# motoko_ice_dragon.net
KiCad netlist of a schematic drawn in EAGLE
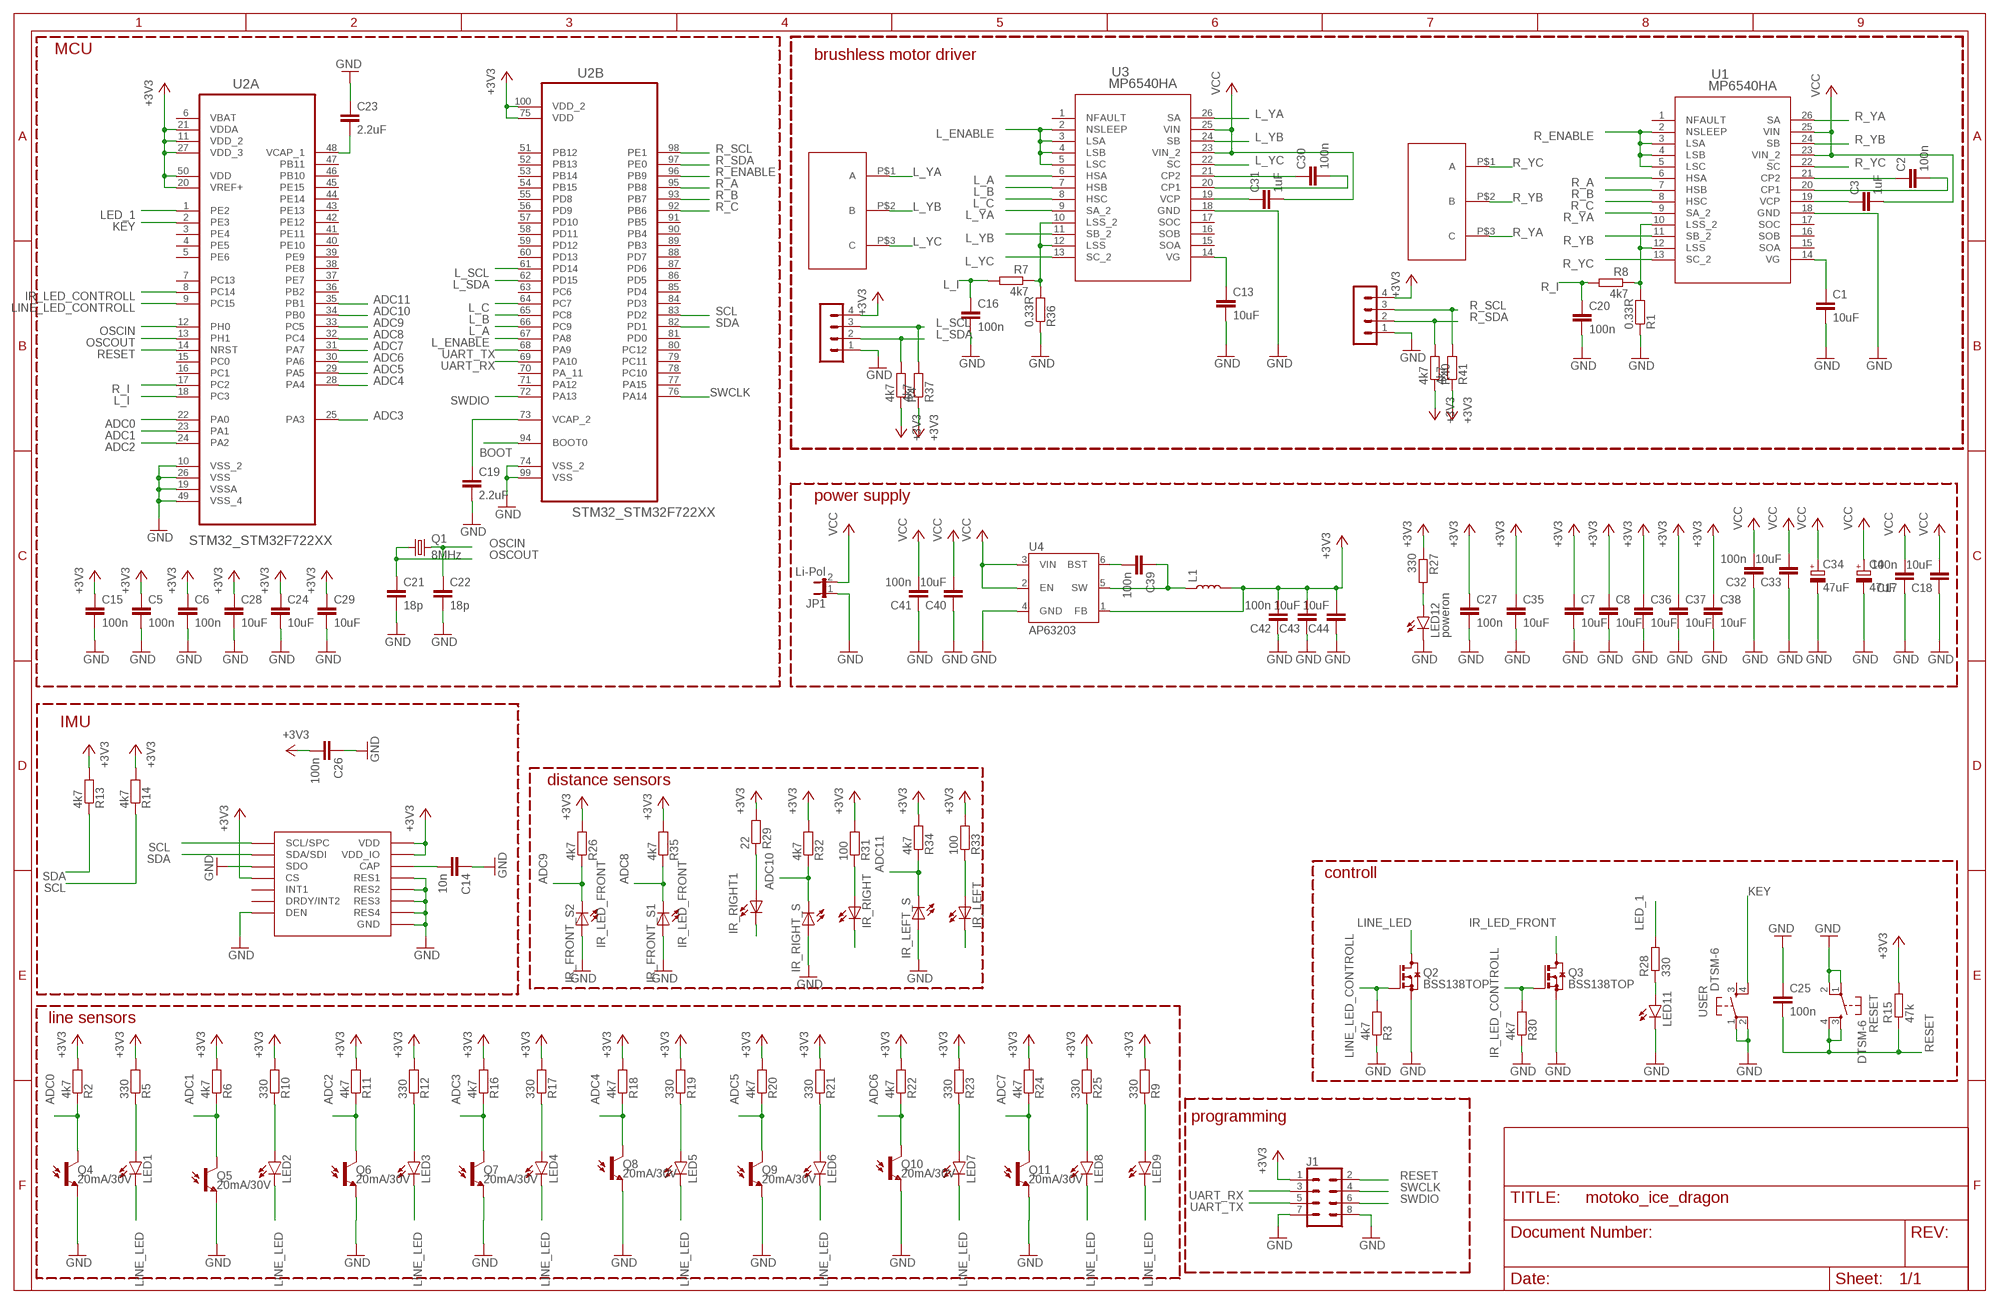
[diagram p0: schematic, sheet 1]

(export (version "E")
  (design (tool "Eeschema 10.0.6"))
  (components
    (comp (ref "C1")
      (value "10uF")
      (footprint "eagle-import:C0805")
      (libsource (lib "eagle-import") (part "C-EUC0805"))
    )
    (comp (ref "C2")
      (value "100n")
      (footprint "eagle-import:C0805")
      (libsource (lib "eagle-import") (part "C-EUC0805"))
    )
    (comp (ref "C3")
      (value "1uF")
      (footprint "eagle-import:C0805")
      (libsource (lib "eagle-import") (part "C-EUC0805"))
    )
    (comp (ref "C4")
      (value "47uF")
      (footprint "eagle-import:140CLH-1010")
      (libsource (lib "eagle-import") (part "CPOL-EU140CLH-1010"))
    )
    (comp (ref "C5")
      (value "100n")
      (footprint "eagle-import:C0805")
      (libsource (lib "eagle-import") (part "C-EUC0805"))
    )
    (comp (ref "C6")
      (value "100n")
      (footprint "eagle-import:C0805")
      (libsource (lib "eagle-import") (part "C-EUC0805"))
    )
    (comp (ref "C7")
      (value "10uF")
      (footprint "eagle-import:C0805")
      (libsource (lib "eagle-import") (part "C-EUC0805"))
    )
    (comp (ref "C8")
      (value "10uF")
      (footprint "eagle-import:C0805")
      (libsource (lib "eagle-import") (part "C-EUC0805"))
    )
    (comp (ref "C13")
      (value "10uF")
      (footprint "eagle-import:C0805")
      (libsource (lib "eagle-import") (part "C-EUC0805"))
    )
    (comp (ref "C14")
      (value "10n")
      (footprint "eagle-import:C0805")
      (libsource (lib "eagle-import") (part "C-EUC0805"))
    )
    (comp (ref "C15")
      (value "100n")
      (footprint "eagle-import:C0805")
      (libsource (lib "eagle-import") (part "C-EUC0805"))
    )
    (comp (ref "C16")
      (value "100n")
      (footprint "eagle-import:C0805")
      (libsource (lib "eagle-import") (part "C-EUC0805"))
    )
    (comp (ref "C17")
      (value "100n")
      (footprint "eagle-import:C0805")
      (libsource (lib "eagle-import") (part "C-EUC0805"))
    )
    (comp (ref "C18")
      (value "10uF")
      (footprint "eagle-import:C0805")
      (libsource (lib "eagle-import") (part "C-EUC0805"))
    )
    (comp (ref "C19")
      (value "2.2uF")
      (footprint "eagle-import:C0805")
      (libsource (lib "eagle-import") (part "C-EUC0805"))
    )
    (comp (ref "C20")
      (value "100n")
      (footprint "eagle-import:C0805")
      (libsource (lib "eagle-import") (part "C-EUC0805"))
    )
    (comp (ref "C21")
      (value "18p")
      (footprint "eagle-import:C0805")
      (libsource (lib "eagle-import") (part "C-EUC0805"))
    )
    (comp (ref "C22")
      (value "18p")
      (footprint "eagle-import:C0805")
      (libsource (lib "eagle-import") (part "C-EUC0805"))
    )
    (comp (ref "C23")
      (value "2.2uF")
      (footprint "eagle-import:C0805")
      (libsource (lib "eagle-import") (part "C-EUC0805"))
    )
    (comp (ref "C24")
      (value "10uF")
      (footprint "eagle-import:C0805")
      (libsource (lib "eagle-import") (part "C-EUC0805"))
    )
    (comp (ref "C25")
      (value "100n")
      (footprint "eagle-import:C0805")
      (libsource (lib "eagle-import") (part "C-EUC0805"))
    )
    (comp (ref "C26")
      (value "100n")
      (footprint "eagle-import:C0805")
      (libsource (lib "eagle-import") (part "C-EUC0805"))
    )
    (comp (ref "C27")
      (value "100n")
      (footprint "eagle-import:C0805")
      (libsource (lib "eagle-import") (part "C-EUC0805"))
    )
    (comp (ref "C28")
      (value "10uF")
      (footprint "eagle-import:C0805")
      (libsource (lib "eagle-import") (part "C-EUC0805"))
    )
    (comp (ref "C29")
      (value "10uF")
      (footprint "eagle-import:C0805")
      (libsource (lib "eagle-import") (part "C-EUC0805"))
    )
    (comp (ref "C30")
      (value "100n")
      (footprint "eagle-import:C0805")
      (libsource (lib "eagle-import") (part "C-EUC0805"))
    )
    (comp (ref "C31")
      (value "1uF")
      (footprint "eagle-import:C0805")
      (libsource (lib "eagle-import") (part "C-EUC0805"))
    )
    (comp (ref "C32")
      (value "100n")
      (footprint "eagle-import:C0805")
      (libsource (lib "eagle-import") (part "C-EUC0805"))
    )
    (comp (ref "C33")
      (value "10uF")
      (footprint "eagle-import:C0805")
      (libsource (lib "eagle-import") (part "C-EUC0805"))
    )
    (comp (ref "C34")
      (value "47uF")
      (footprint "eagle-import:140CLH-1010")
      (libsource (lib "eagle-import") (part "CPOL-EU140CLH-1010"))
    )
    (comp (ref "C35")
      (value "10uF")
      (footprint "eagle-import:C0805")
      (libsource (lib "eagle-import") (part "C-EUC0805"))
    )
    (comp (ref "C36")
      (value "10uF")
      (footprint "eagle-import:C0805")
      (libsource (lib "eagle-import") (part "C-EUC0805"))
    )
    (comp (ref "C37")
      (value "10uF")
      (footprint "eagle-import:C0805")
      (libsource (lib "eagle-import") (part "C-EUC0805"))
    )
    (comp (ref "C38")
      (value "10uF")
      (footprint "eagle-import:C0805")
      (libsource (lib "eagle-import") (part "C-EUC0805"))
    )
    (comp (ref "C39")
      (value "100n")
      (footprint "eagle-import:C0805")
      (libsource (lib "eagle-import") (part "C-EUC0805"))
    )
    (comp (ref "C40")
      (value "10uF")
      (footprint "eagle-import:C0805")
      (libsource (lib "eagle-import") (part "C-EUC0805"))
    )
    (comp (ref "C41")
      (value "100n")
      (footprint "eagle-import:C0805")
      (libsource (lib "eagle-import") (part "C-EUC0805"))
    )
    (comp (ref "C42")
      (value "100n")
      (footprint "eagle-import:C0805")
      (libsource (lib "eagle-import") (part "C-EUC0805"))
    )
    (comp (ref "C43")
      (value "10uF")
      (footprint "eagle-import:C0805")
      (libsource (lib "eagle-import") (part "C-EUC0805"))
    )
    (comp (ref "C44")
      (value "10uF")
      (footprint "eagle-import:C0805")
      (libsource (lib "eagle-import") (part "C-EUC0805"))
    )
    (comp (ref "IR_FRONT_S1")
      (value "LED5MM")
      (footprint "eagle-import:LED5MM")
      (libsource (lib "eagle-import") (part "my_parts_LED5MM"))
    )
    (comp (ref "IR_FRONT_S2")
      (value "LED5MM")
      (footprint "eagle-import:LED5MM")
      (libsource (lib "eagle-import") (part "my_parts_LED5MM"))
    )
    (comp (ref "IR_LEFT")
      (value "LED5MM")
      (footprint "eagle-import:LED5MM")
      (libsource (lib "eagle-import") (part "my_parts_LED5MM"))
    )
    (comp (ref "IR_LEFT_S")
      (value "LED5MM")
      (footprint "eagle-import:LED5MM")
      (libsource (lib "eagle-import") (part "my_parts_LED5MM"))
    )
    (comp (ref "IR_RIGHT")
      (value "LED5MM")
      (footprint "eagle-import:LED5MM")
      (libsource (lib "eagle-import") (part "my_parts_LED5MM"))
    )
    (comp (ref "IR_RIGHT1")
      (value "LED5MM")
      (footprint "eagle-import:LED5MM")
      (libsource (lib "eagle-import") (part "my_parts_LED5MM"))
    )
    (comp (ref "IR_RIGHT_S")
      (value "LED5MM")
      (footprint "eagle-import:LED5MM")
      (libsource (lib "eagle-import") (part "my_parts_LED5MM"))
    )
    (comp (ref "J1")
      (value "CONN_04X2")
      (footprint "eagle-import:2X4")
      (libsource (lib "eagle-import") (part "CONN_04X2"))
    )
    (comp (ref "JP1")
      (value "Li-Pol")
      (footprint "eagle-import:JP1")
      (libsource (lib "eagle-import") (part "JP1E"))
    )
    (comp (ref "L1")
      (value "4.7uH, TYS50204R7N-10")
      (footprint "eagle-import:CR54")
      (libsource (lib "eagle-import") (part "INDUCTOR-CR54-3.3UH"))
    )
    (comp (ref "LED1")
      (value "LEDCHIPLED_1206")
      (footprint "eagle-import:CHIPLED_1206")
      (libsource (lib "eagle-import") (part "LEDCHIPLED_1206"))
    )
    (comp (ref "LED2")
      (value "LEDCHIPLED_1206")
      (footprint "eagle-import:CHIPLED_1206")
      (libsource (lib "eagle-import") (part "LEDCHIPLED_1206"))
    )
    (comp (ref "LED3")
      (value "LEDCHIPLED_1206")
      (footprint "eagle-import:CHIPLED_1206")
      (libsource (lib "eagle-import") (part "LEDCHIPLED_1206"))
    )
    (comp (ref "LED4")
      (value "LEDCHIPLED_1206")
      (footprint "eagle-import:CHIPLED_1206")
      (libsource (lib "eagle-import") (part "LEDCHIPLED_1206"))
    )
    (comp (ref "LED5")
      (value "LEDCHIPLED_1206")
      (footprint "eagle-import:CHIPLED_1206")
      (libsource (lib "eagle-import") (part "LEDCHIPLED_1206"))
    )
    (comp (ref "LED6")
      (value "LEDCHIPLED_1206")
      (footprint "eagle-import:CHIPLED_1206")
      (libsource (lib "eagle-import") (part "LEDCHIPLED_1206"))
    )
    (comp (ref "LED7")
      (value "LEDCHIPLED_1206")
      (footprint "eagle-import:CHIPLED_1206")
      (libsource (lib "eagle-import") (part "LEDCHIPLED_1206"))
    )
    (comp (ref "LED8")
      (value "LEDCHIPLED_1206")
      (footprint "eagle-import:CHIPLED_1206")
      (libsource (lib "eagle-import") (part "LEDCHIPLED_1206"))
    )
    (comp (ref "LED9")
      (value "LEDCHIPLED_1206")
      (footprint "eagle-import:CHIPLED_1206")
      (libsource (lib "eagle-import") (part "LEDCHIPLED_1206"))
    )
    (comp (ref "LED11")
      (value "LEDCHIPLED_1206")
      (footprint "eagle-import:CHIPLED_1206")
      (libsource (lib "eagle-import") (part "LEDCHIPLED_1206"))
    )
    (comp (ref "LED12")
      (value "poweron")
      (footprint "eagle-import:CHIPLED_1206")
      (libsource (lib "eagle-import") (part "LEDCHIPLED_1206"))
    )
    (comp (ref "LSM6DS1")
      (value "ST_L3GD20H")
      (footprint "eagle-import:ST_LGA16L")
      (libsource (lib "eagle-import") (part "ST_L3GD20H"))
    )
    (comp (ref "L_ENCODER")
      (value "MA04-1")
      (footprint "eagle-import:MA04-1")
      (libsource (lib "eagle-import") (part "MA04-1"))
    )
    (comp (ref "L_ENCODER1")
      (value "MA04-1")
      (footprint "eagle-import:MA04-1")
      (libsource (lib "eagle-import") (part "MA04-1"))
    )
    (comp (ref "Q1")
      (value "8MHz")
      (footprint "eagle-import:CTS406")
      (libsource (lib "eagle-import") (part "CRYSTALCTS406"))
    )
    (comp (ref "Q2")
      (value "BSS138TOP")
      (footprint "eagle-import:SOT23")
      (libsource (lib "eagle-import") (part "BSS138TOP"))
    )
    (comp (ref "Q3")
      (value "BSS138TOP")
      (footprint "eagle-import:SOT23")
      (libsource (lib "eagle-import") (part "BSS138TOP"))
    )
    (comp (ref "Q4")
      (value "20mA/30V")
      (footprint "eagle-import:PT17-21C-L41-TR8")
      (libsource (lib "eagle-import") (part "PHOTOTRANSISTORPT17-21C-L41-TR8"))
    )
    (comp (ref "Q5")
      (value "20mA/30V")
      (footprint "eagle-import:PT17-21C-L41-TR8")
      (libsource (lib "eagle-import") (part "PHOTOTRANSISTORPT17-21C-L41-TR8"))
    )
    (comp (ref "Q6")
      (value "20mA/30V")
      (footprint "eagle-import:PT17-21C-L41-TR8")
      (libsource (lib "eagle-import") (part "PHOTOTRANSISTORPT17-21C-L41-TR8"))
    )
    (comp (ref "Q7")
      (value "20mA/30V")
      (footprint "eagle-import:PT17-21C-L41-TR8")
      (libsource (lib "eagle-import") (part "PHOTOTRANSISTORPT17-21C-L41-TR8"))
    )
    (comp (ref "Q8")
      (value "20mA/30V")
      (footprint "eagle-import:PT17-21C-L41-TR8")
      (libsource (lib "eagle-import") (part "PHOTOTRANSISTORPT17-21C-L41-TR8"))
    )
    (comp (ref "Q9")
      (value "20mA/30V")
      (footprint "eagle-import:PT17-21C-L41-TR8")
      (libsource (lib "eagle-import") (part "PHOTOTRANSISTORPT17-21C-L41-TR8"))
    )
    (comp (ref "Q10")
      (value "20mA/30V")
      (footprint "eagle-import:PT17-21C-L41-TR8")
      (libsource (lib "eagle-import") (part "PHOTOTRANSISTORPT17-21C-L41-TR8"))
    )
    (comp (ref "Q11")
      (value "20mA/30V")
      (footprint "eagle-import:PT17-21C-L41-TR8")
      (libsource (lib "eagle-import") (part "PHOTOTRANSISTORPT17-21C-L41-TR8"))
    )
    (comp (ref "R1")
      (value "0.33R")
      (footprint "eagle-import:M0805")
      (libsource (lib "eagle-import") (part "R-EU_M0805"))
    )
    (comp (ref "R2")
      (value "4k7")
      (footprint "eagle-import:M0805")
      (libsource (lib "eagle-import") (part "R-EU_M0805"))
    )
    (comp (ref "R3")
      (value "4k7")
      (footprint "eagle-import:M0805")
      (libsource (lib "eagle-import") (part "R-EU_M0805"))
    )
    (comp (ref "R4")
      (value "4k7")
      (footprint "eagle-import:M0805")
      (libsource (lib "eagle-import") (part "R-EU_M0805"))
    )
    (comp (ref "R5")
      (value "330")
      (footprint "eagle-import:M0805")
      (libsource (lib "eagle-import") (part "R-EU_M0805"))
    )
    (comp (ref "R6")
      (value "4k7")
      (footprint "eagle-import:M0805")
      (libsource (lib "eagle-import") (part "R-EU_M0805"))
    )
    (comp (ref "R7")
      (value "4k7")
      (footprint "eagle-import:M0805")
      (libsource (lib "eagle-import") (part "R-EU_M0805"))
    )
    (comp (ref "R8")
      (value "4k7")
      (footprint "eagle-import:M0805")
      (libsource (lib "eagle-import") (part "R-EU_M0805"))
    )
    (comp (ref "R9")
      (value "330")
      (footprint "eagle-import:M0805")
      (libsource (lib "eagle-import") (part "R-EU_M0805"))
    )
    (comp (ref "R10")
      (value "330")
      (footprint "eagle-import:M0805")
      (libsource (lib "eagle-import") (part "R-EU_M0805"))
    )
    (comp (ref "R11")
      (value "4k7")
      (footprint "eagle-import:M0805")
      (libsource (lib "eagle-import") (part "R-EU_M0805"))
    )
    (comp (ref "R12")
      (value "330")
      (footprint "eagle-import:M0805")
      (libsource (lib "eagle-import") (part "R-EU_M0805"))
    )
    (comp (ref "R13")
      (value "4k7")
      (footprint "eagle-import:M0805")
      (libsource (lib "eagle-import") (part "R-EU_M0805"))
    )
    (comp (ref "R14")
      (value "4k7")
      (footprint "eagle-import:M0805")
      (libsource (lib "eagle-import") (part "R-EU_M0805"))
    )
    (comp (ref "R15")
      (value "47k")
      (footprint "eagle-import:M0805")
      (libsource (lib "eagle-import") (part "R-EU_M0805"))
    )
    (comp (ref "R16")
      (value "4k7")
      (footprint "eagle-import:M0805")
      (libsource (lib "eagle-import") (part "R-EU_M0805"))
    )
    (comp (ref "R17")
      (value "330")
      (footprint "eagle-import:M0805")
      (libsource (lib "eagle-import") (part "R-EU_M0805"))
    )
    (comp (ref "R18")
      (value "4k7")
      (footprint "eagle-import:M0805")
      (libsource (lib "eagle-import") (part "R-EU_M0805"))
    )
    (comp (ref "R19")
      (value "330")
      (footprint "eagle-import:M0805")
      (libsource (lib "eagle-import") (part "R-EU_M0805"))
    )
    (comp (ref "R20")
      (value "4k7")
      (footprint "eagle-import:M0805")
      (libsource (lib "eagle-import") (part "R-EU_M0805"))
    )
    (comp (ref "R21")
      (value "330")
      (footprint "eagle-import:M0805")
      (libsource (lib "eagle-import") (part "R-EU_M0805"))
    )
    (comp (ref "R22")
      (value "4k7")
      (footprint "eagle-import:M0805")
      (libsource (lib "eagle-import") (part "R-EU_M0805"))
    )
    (comp (ref "R23")
      (value "330")
      (footprint "eagle-import:M0805")
      (libsource (lib "eagle-import") (part "R-EU_M0805"))
    )
    (comp (ref "R24")
      (value "4k7")
      (footprint "eagle-import:M0805")
      (libsource (lib "eagle-import") (part "R-EU_M0805"))
    )
    (comp (ref "R25")
      (value "330")
      (footprint "eagle-import:M0805")
      (libsource (lib "eagle-import") (part "R-EU_M0805"))
    )
    (comp (ref "R26")
      (value "4k7")
      (footprint "eagle-import:M0805")
      (libsource (lib "eagle-import") (part "R-EU_M0805"))
    )
    (comp (ref "R27")
      (value "330")
      (footprint "eagle-import:M0805")
      (libsource (lib "eagle-import") (part "R-EU_M0805"))
    )
    (comp (ref "R28")
      (value "330")
      (footprint "eagle-import:M0805")
      (libsource (lib "eagle-import") (part "R-EU_M0805"))
    )
    (comp (ref "R29")
      (value "22")
      (footprint "eagle-import:M0805")
      (libsource (lib "eagle-import") (part "R-EU_M0805"))
    )
    (comp (ref "R30")
      (value "4k7")
      (footprint "eagle-import:M0805")
      (libsource (lib "eagle-import") (part "R-EU_M0805"))
    )
    (comp (ref "R31")
      (value "100")
      (footprint "eagle-import:M0805")
      (libsource (lib "eagle-import") (part "R-EU_M0805"))
    )
    (comp (ref "R32")
      (value "4k7")
      (footprint "eagle-import:M0805")
      (libsource (lib "eagle-import") (part "R-EU_M0805"))
    )
    (comp (ref "R33")
      (value "100")
      (footprint "eagle-import:M0805")
      (libsource (lib "eagle-import") (part "R-EU_M0805"))
    )
    (comp (ref "R34")
      (value "4k7")
      (footprint "eagle-import:M0805")
      (libsource (lib "eagle-import") (part "R-EU_M0805"))
    )
    (comp (ref "R35")
      (value "4k7")
      (footprint "eagle-import:M0805")
      (libsource (lib "eagle-import") (part "R-EU_M0805"))
    )
    (comp (ref "R36")
      (value "0.33R")
      (footprint "eagle-import:M0805")
      (libsource (lib "eagle-import") (part "R-EU_M0805"))
    )
    (comp (ref "R37")
      (value "4k7")
      (footprint "eagle-import:M0805")
      (libsource (lib "eagle-import") (part "R-EU_M0805"))
    )
    (comp (ref "R40")
      (value "4k7")
      (footprint "eagle-import:M0805")
      (libsource (lib "eagle-import") (part "R-EU_M0805"))
    )
    (comp (ref "R41")
      (value "4k7")
      (footprint "eagle-import:M0805")
      (libsource (lib "eagle-import") (part "R-EU_M0805"))
    )
    (comp (ref "RESET")
      (value "DTSM-6")
      (footprint "eagle-import:DTSM-6")
      (libsource (lib "eagle-import") (part "DTSM-6"))
    )
    (comp (ref "U$1")
      (value "BRUSHLESS_GIMBAL_MOTOR_WHEEL")
      (footprint "eagle-import:BRUSHLESS_GIMBAL_MOTOR_WHEEL")
      (libsource (lib "eagle-import") (part "BRUSHLESS_GIMBAL_MOTOR_WHEEL"))
    )
    (comp (ref "U$2")
      (value "BRUSHLESS_GIMBAL_MOTOR_WHEEL")
      (footprint "eagle-import:BRUSHLESS_GIMBAL_MOTOR_WHEEL")
      (libsource (lib "eagle-import") (part "BRUSHLESS_GIMBAL_MOTOR_WHEEL"))
    )
    (comp (ref "U1")
      (value "MP6540HA")
      (footprint "eagle-import:QFN-5X5_MP6540HA_MNP")
      (fields (field (name "COPYRIGHT") "Copyright (C) 2018 Accelerated Designs. All rights reserved"))
      (libsource (lib "eagle-import") (part "MP6540HA"))
    )
    (comp (ref "U2")
      (value "STM32_STM32F722XX")
      (footprint "eagle-import:STM32_QFP50P1600X1600X160-100N")
      (fields (field (name "MPN") "STM32F407VET6"))
      (libsource (lib "eagle-import") (part "STM32_STM32F722XX"))
    )
    (comp (ref "U3")
      (value "MP6540HA")
      (footprint "eagle-import:QFN-5X5_MP6540HA_MNP")
      (fields (field (name "COPYRIGHT") "Copyright (C) 2018 Accelerated Designs. All rights reserved"))
      (libsource (lib "eagle-import") (part "MP6540HA"))
    )
    (comp (ref "U4")
      (value "AP63203")
      (footprint "eagle-import:SOT23-6")
      (libsource (lib "eagle-import") (part "AP63203"))
    )
    (comp (ref "USER")
      (value "DTSM-6")
      (footprint "eagle-import:DTSM-6")
      (libsource (lib "eagle-import") (part "DTSM-6"))
    )
  )
  (nets
    (net (code "1") (name "+3V3") (class "Default")
      (node (ref "C15") (pin "1") (pinfunction "1_1") (pintype "passive"))
      (node (ref "C24") (pin "1") (pinfunction "1_1") (pintype "passive"))
      (node (ref "C26") (pin "2") (pinfunction "2_2") (pintype "passive"))
      (node (ref "C27") (pin "1") (pinfunction "1_1") (pintype "passive"))
      (node (ref "C28") (pin "1") (pinfunction "1_1") (pintype "passive"))
      (node (ref "C29") (pin "1") (pinfunction "1_1") (pintype "passive"))
      (node (ref "C35") (pin "1") (pinfunction "1_1") (pintype "passive"))
      (node (ref "C36") (pin "1") (pinfunction "1_1") (pintype "passive"))
      (node (ref "C37") (pin "1") (pinfunction "1_1") (pintype "passive"))
      (node (ref "C38") (pin "1") (pinfunction "1_1") (pintype "passive"))
      (node (ref "C42") (pin "2") (pinfunction "2_2") (pintype "passive"))
      (node (ref "C43") (pin "2") (pinfunction "2_2") (pintype "passive"))
      (node (ref "C44") (pin "2") (pinfunction "2_2") (pintype "passive"))
      (node (ref "C5") (pin "1") (pinfunction "1_1") (pintype "passive"))
      (node (ref "C6") (pin "1") (pinfunction "1_1") (pintype "passive"))
      (node (ref "C7") (pin "1") (pinfunction "1_1") (pintype "passive"))
      (node (ref "C8") (pin "1") (pinfunction "1_1") (pintype "passive"))
      (node (ref "J1") (pin "1") (pinfunction "1_1") (pintype "passive"))
      (node (ref "L1") (pin "P$2") (pinfunction "2_P$2") (pintype "passive"))
      (node (ref "LSM6DS1") (pin "P$1") (pinfunction "VDD_IO_P$1") (pintype "power_in"))
      (node (ref "LSM6DS1") (pin "P$16") (pinfunction "VDD_P$16") (pintype "power_in"))
      (node (ref "LSM6DS1") (pin "P$5") (pinfunction "CS_P$5") (pintype "bidirectional"))
      (node (ref "L_ENCODER") (pin "4") (pinfunction "4_4") (pintype "passive"))
      (node (ref "L_ENCODER1") (pin "4") (pinfunction "4_4") (pintype "passive"))
      (node (ref "R10") (pin "2") (pinfunction "2_2") (pintype "passive"))
      (node (ref "R11") (pin "2") (pinfunction "2_2") (pintype "passive"))
      (node (ref "R12") (pin "2") (pinfunction "2_2") (pintype "passive"))
      (node (ref "R13") (pin "2") (pinfunction "2_2") (pintype "passive"))
      (node (ref "R14") (pin "2") (pinfunction "2_2") (pintype "passive"))
      (node (ref "R15") (pin "2") (pinfunction "2_2") (pintype "passive"))
      (node (ref "R16") (pin "2") (pinfunction "2_2") (pintype "passive"))
      (node (ref "R17") (pin "2") (pinfunction "2_2") (pintype "passive"))
      (node (ref "R18") (pin "2") (pinfunction "2_2") (pintype "passive"))
      (node (ref "R19") (pin "2") (pinfunction "2_2") (pintype "passive"))
      (node (ref "R2") (pin "2") (pinfunction "2_2") (pintype "passive"))
      (node (ref "R20") (pin "2") (pinfunction "2_2") (pintype "passive"))
      (node (ref "R21") (pin "2") (pinfunction "2_2") (pintype "passive"))
      (node (ref "R22") (pin "2") (pinfunction "2_2") (pintype "passive"))
      (node (ref "R23") (pin "2") (pinfunction "2_2") (pintype "passive"))
      (node (ref "R24") (pin "2") (pinfunction "2_2") (pintype "passive"))
      (node (ref "R25") (pin "2") (pinfunction "2_2") (pintype "passive"))
      (node (ref "R26") (pin "2") (pinfunction "2_2") (pintype "passive"))
      (node (ref "R27") (pin "1") (pinfunction "1_1") (pintype "passive"))
      (node (ref "R29") (pin "2") (pinfunction "2_2") (pintype "passive"))
      (node (ref "R31") (pin "2") (pinfunction "2_2") (pintype "passive"))
      (node (ref "R32") (pin "2") (pinfunction "2_2") (pintype "passive"))
      (node (ref "R33") (pin "2") (pinfunction "2_2") (pintype "passive"))
      (node (ref "R34") (pin "2") (pinfunction "2_2") (pintype "passive"))
      (node (ref "R35") (pin "2") (pinfunction "2_2") (pintype "passive"))
      (node (ref "R37") (pin "1") (pinfunction "1_1") (pintype "passive"))
      (node (ref "R4") (pin "1") (pinfunction "1_1") (pintype "passive"))
      (node (ref "R40") (pin "1") (pinfunction "1_1") (pintype "passive"))
      (node (ref "R41") (pin "1") (pinfunction "1_1") (pintype "passive"))
      (node (ref "R5") (pin "2") (pinfunction "2_2") (pintype "passive"))
      (node (ref "R6") (pin "2") (pinfunction "2_2") (pintype "passive"))
      (node (ref "R9") (pin "2") (pinfunction "2_2") (pintype "passive"))
      (node (ref "U2") (pin "100") (pinfunction "VDD_2_100") (pintype "power_in"))
      (node (ref "U2") (pin "11") (pinfunction "VDD_2_11") (pintype "power_in"))
      (node (ref "U2") (pin "20") (pinfunction "VREF+_20") (pintype "power_in"))
      (node (ref "U2") (pin "21") (pinfunction "VDDA_21") (pintype "power_in"))
      (node (ref "U2") (pin "27") (pinfunction "VDD_3_27") (pintype "power_in"))
      (node (ref "U2") (pin "50") (pinfunction "VDD_50") (pintype "power_in"))
      (node (ref "U2") (pin "75") (pinfunction "VDD_75") (pintype "power_in"))
      (node (ref "U4") (pin "1") (pinfunction "FB_1") (pintype "bidirectional"))
    )
    (net (code "2") (name "/ADC0") (class "Default")
      (node (ref "Q4") (pin "C") (pinfunction "C_C") (pintype "passive"))
      (node (ref "R2") (pin "1") (pinfunction "1_1") (pintype "passive"))
      (node (ref "U2") (pin "22") (pinfunction "PA0_22") (pintype "bidirectional"))
    )
    (net (code "3") (name "/ADC1") (class "Default")
      (node (ref "Q5") (pin "C") (pinfunction "C_C") (pintype "passive"))
      (node (ref "R6") (pin "1") (pinfunction "1_1") (pintype "passive"))
      (node (ref "U2") (pin "23") (pinfunction "PA1_23") (pintype "bidirectional"))
    )
    (net (code "4") (name "/ADC2") (class "Default")
      (node (ref "Q6") (pin "C") (pinfunction "C_C") (pintype "passive"))
      (node (ref "R11") (pin "1") (pinfunction "1_1") (pintype "passive"))
      (node (ref "U2") (pin "24") (pinfunction "PA2_24") (pintype "bidirectional"))
    )
    (net (code "5") (name "/ADC3") (class "Default")
      (node (ref "Q7") (pin "C") (pinfunction "C_C") (pintype "passive"))
      (node (ref "R16") (pin "1") (pinfunction "1_1") (pintype "passive"))
      (node (ref "U2") (pin "25") (pinfunction "PA3_25") (pintype "bidirectional"))
    )
    (net (code "6") (name "/ADC4") (class "Default")
      (node (ref "Q8") (pin "C") (pinfunction "C_C") (pintype "passive"))
      (node (ref "R18") (pin "1") (pinfunction "1_1") (pintype "passive"))
      (node (ref "U2") (pin "28") (pinfunction "PA4_28") (pintype "bidirectional"))
    )
    (net (code "7") (name "/ADC5") (class "Default")
      (node (ref "Q9") (pin "C") (pinfunction "C_C") (pintype "passive"))
      (node (ref "R20") (pin "1") (pinfunction "1_1") (pintype "passive"))
      (node (ref "U2") (pin "29") (pinfunction "PA5_29") (pintype "bidirectional"))
    )
    (net (code "8") (name "/ADC6") (class "Default")
      (node (ref "Q10") (pin "C") (pinfunction "C_C") (pintype "passive"))
      (node (ref "R22") (pin "1") (pinfunction "1_1") (pintype "passive"))
      (node (ref "U2") (pin "30") (pinfunction "PA6_30") (pintype "bidirectional"))
    )
    (net (code "9") (name "/ADC7") (class "Default")
      (node (ref "Q11") (pin "C") (pinfunction "C_C") (pintype "passive"))
      (node (ref "R24") (pin "1") (pinfunction "1_1") (pintype "passive"))
      (node (ref "U2") (pin "31") (pinfunction "PA7_31") (pintype "bidirectional"))
    )
    (net (code "10") (name "/ADC8") (class "Default")
      (node (ref "IR_FRONT_S1") (pin "K") (pinfunction "C_K") (pintype "passive"))
      (node (ref "R35") (pin "1") (pinfunction "1_1") (pintype "passive"))
      (node (ref "U2") (pin "32") (pinfunction "PC4_32") (pintype "bidirectional"))
    )
    (net (code "11") (name "/ADC9") (class "Default")
      (node (ref "IR_FRONT_S2") (pin "K") (pinfunction "C_K") (pintype "passive"))
      (node (ref "R26") (pin "1") (pinfunction "1_1") (pintype "passive"))
      (node (ref "U2") (pin "33") (pinfunction "PC5_33") (pintype "bidirectional"))
    )
    (net (code "12") (name "/ADC10") (class "Default")
      (node (ref "IR_RIGHT_S") (pin "K") (pinfunction "C_K") (pintype "passive"))
      (node (ref "R32") (pin "1") (pinfunction "1_1") (pintype "passive"))
      (node (ref "U2") (pin "34") (pinfunction "PB0_34") (pintype "bidirectional"))
    )
    (net (code "13") (name "/ADC11") (class "Default")
      (node (ref "IR_LEFT_S") (pin "K") (pinfunction "C_K") (pintype "passive"))
      (node (ref "R34") (pin "1") (pinfunction "1_1") (pintype "passive"))
      (node (ref "U2") (pin "35") (pinfunction "PB1_35") (pintype "bidirectional"))
    )
    (net (code "14") (name "/BOOT") (class "Default")
      (node (ref "U2") (pin "94") (pinfunction "BOOT0_94") (pintype "input"))
    )
    (net (code "15") (name "/IR_LED_CONTROLL") (class "Default")
      (node (ref "Q3") (pin "1") (pinfunction "G_1") (pintype "passive"))
      (node (ref "R30") (pin "2") (pinfunction "2_2") (pintype "passive"))
      (node (ref "U2") (pin "8") (pinfunction "PC14_8") (pintype "bidirectional"))
    )
    (net (code "16") (name "/IR_LED_FRONT") (class "Default")
      (node (ref "IR_LEFT") (pin "K") (pinfunction "C_K") (pintype "passive"))
      (node (ref "IR_RIGHT") (pin "K") (pinfunction "C_K") (pintype "passive"))
      (node (ref "IR_RIGHT1") (pin "K") (pinfunction "C_K") (pintype "passive"))
      (node (ref "Q3") (pin "3") (pinfunction "D_3") (pintype "passive"))
    )
    (net (code "17") (name "/KEY") (class "Default")
      (node (ref "U2") (pin "2") (pinfunction "PE3_2") (pintype "bidirectional"))
      (node (ref "USER") (pin "4") (pinfunction "4_4") (pintype "passive"))
    )
    (net (code "18") (name "/LED_1") (class "Default")
      (node (ref "R28") (pin "2") (pinfunction "2_2") (pintype "passive"))
      (node (ref "U2") (pin "1") (pinfunction "PE2_1") (pintype "bidirectional"))
    )
    (net (code "19") (name "/LINE_LED") (class "Default")
      (node (ref "LED1") (pin "C") (pinfunction "C_C") (pintype "passive"))
      (node (ref "LED2") (pin "C") (pinfunction "C_C") (pintype "passive"))
      (node (ref "LED3") (pin "C") (pinfunction "C_C") (pintype "passive"))
      (node (ref "LED4") (pin "C") (pinfunction "C_C") (pintype "passive"))
      (node (ref "LED5") (pin "C") (pinfunction "C_C") (pintype "passive"))
      (node (ref "LED6") (pin "C") (pinfunction "C_C") (pintype "passive"))
      (node (ref "LED7") (pin "C") (pinfunction "C_C") (pintype "passive"))
      (node (ref "LED8") (pin "C") (pinfunction "C_C") (pintype "passive"))
      (node (ref "LED9") (pin "C") (pinfunction "C_C") (pintype "passive"))
      (node (ref "Q2") (pin "3") (pinfunction "D_3") (pintype "passive"))
    )
    (net (code "20") (name "/LINE_LED_CONTROLL") (class "Default")
      (node (ref "Q2") (pin "1") (pinfunction "G_1") (pintype "passive"))
      (node (ref "R3") (pin "2") (pinfunction "2_2") (pintype "passive"))
      (node (ref "U2") (pin "9") (pinfunction "PC15_9") (pintype "bidirectional"))
    )
    (net (code "21") (name "/L_A") (class "Default")
      (node (ref "U2") (pin "66") (pinfunction "PC9_66") (pintype "bidirectional"))
      (node (ref "U3") (pin "6") (pinfunction "HSA_6") (pintype "passive"))
    )
    (net (code "22") (name "/L_B") (class "Default")
      (node (ref "U2") (pin "65") (pinfunction "PC8_65") (pintype "bidirectional"))
      (node (ref "U3") (pin "7") (pinfunction "HSB_7") (pintype "passive"))
    )
    (net (code "23") (name "/L_C") (class "Default")
      (node (ref "U2") (pin "64") (pinfunction "PC7_64") (pintype "bidirectional"))
      (node (ref "U3") (pin "8") (pinfunction "HSC_8") (pintype "passive"))
    )
    (net (code "24") (name "/L_ENABLE") (class "Default")
      (node (ref "U2") (pin "67") (pinfunction "PA8_67") (pintype "bidirectional"))
      (node (ref "U3") (pin "2") (pinfunction "NSLEEP_2") (pintype "input"))
      (node (ref "U3") (pin "3") (pinfunction "LSA_3") (pintype "passive"))
      (node (ref "U3") (pin "4") (pinfunction "LSB_4") (pintype "passive"))
      (node (ref "U3") (pin "5") (pinfunction "LSC_5") (pintype "passive"))
    )
    (net (code "25") (name "/L_I") (class "Default")
      (node (ref "C16") (pin "1") (pinfunction "1_1") (pintype "passive"))
      (node (ref "R7") (pin "2") (pinfunction "2_2") (pintype "passive"))
      (node (ref "U2") (pin "18") (pinfunction "PC3_18") (pintype "bidirectional"))
    )
    (net (code "26") (name "/L_SCL") (class "Default")
      (node (ref "L_ENCODER") (pin "3") (pinfunction "3_3") (pintype "passive"))
      (node (ref "R37") (pin "2") (pinfunction "2_2") (pintype "passive"))
      (node (ref "U2") (pin "61") (pinfunction "PD14_61") (pintype "bidirectional"))
    )
    (net (code "27") (name "/L_SDA") (class "Default")
      (node (ref "L_ENCODER") (pin "2") (pinfunction "2_2") (pintype "passive"))
      (node (ref "R4") (pin "2") (pinfunction "2_2") (pintype "passive"))
      (node (ref "U2") (pin "62") (pinfunction "PD15_62") (pintype "bidirectional"))
    )
    (net (code "28") (name "/L_YA") (class "Default")
      (node (ref "U$1") (pin "P$1") (pinfunction "A_P$1") (pintype "input"))
      (node (ref "U3") (pin "26") (pinfunction "SA_26") (pintype "output"))
      (node (ref "U3") (pin "9") (pinfunction "SA_2_9") (pintype "output"))
    )
    (net (code "29") (name "/L_YB") (class "Default")
      (node (ref "U$1") (pin "P$2") (pinfunction "B_P$2") (pintype "input"))
      (node (ref "U3") (pin "11") (pinfunction "SB_2_11") (pintype "output"))
      (node (ref "U3") (pin "24") (pinfunction "SB_24") (pintype "output"))
    )
    (net (code "30") (name "/L_YC") (class "Default")
      (node (ref "U$1") (pin "P$3") (pinfunction "C_P$3") (pintype "input"))
      (node (ref "U3") (pin "13") (pinfunction "SC_2_13") (pintype "output"))
      (node (ref "U3") (pin "22") (pinfunction "SC_22") (pintype "output"))
    )
    (net (code "31") (name "/OSCIN") (class "Default")
      (node (ref "C22") (pin "1") (pinfunction "1_1") (pintype "passive"))
      (node (ref "Q1") (pin "3") (pinfunction "2_3") (pintype "passive"))
      (node (ref "U2") (pin "12") (pinfunction "PH0_12") (pintype "bidirectional"))
    )
    (net (code "32") (name "/OSCOUT") (class "Default")
      (node (ref "C21") (pin "1") (pinfunction "1_1") (pintype "passive"))
      (node (ref "Q1") (pin "1") (pinfunction "1_1") (pintype "passive"))
      (node (ref "U2") (pin "13") (pinfunction "PH1_13") (pintype "bidirectional"))
    )
    (net (code "33") (name "/RESET") (class "Default")
      (node (ref "C25") (pin "2") (pinfunction "2_2") (pintype "passive"))
      (node (ref "J1") (pin "2") (pinfunction "2_2") (pintype "passive"))
      (node (ref "R15") (pin "1") (pinfunction "1_1") (pintype "passive"))
      (node (ref "RESET") (pin "3") (pinfunction "3_3") (pintype "passive"))
      (node (ref "RESET") (pin "4") (pinfunction "4_4") (pintype "passive"))
      (node (ref "U2") (pin "14") (pinfunction "NRST_14") (pintype "bidirectional"))
    )
    (net (code "34") (name "/R_A") (class "Default")
      (node (ref "U1") (pin "6") (pinfunction "HSA_6") (pintype "passive"))
      (node (ref "U2") (pin "95") (pinfunction "PB8_95") (pintype "bidirectional"))
    )
    (net (code "35") (name "/R_B") (class "Default")
      (node (ref "U1") (pin "7") (pinfunction "HSB_7") (pintype "passive"))
      (node (ref "U2") (pin "93") (pinfunction "PB7_93") (pintype "bidirectional"))
    )
    (net (code "36") (name "/R_C") (class "Default")
      (node (ref "U1") (pin "8") (pinfunction "HSC_8") (pintype "passive"))
      (node (ref "U2") (pin "92") (pinfunction "PB6_92") (pintype "bidirectional"))
    )
    (net (code "37") (name "/R_ENABLE") (class "Default")
      (node (ref "U1") (pin "2") (pinfunction "NSLEEP_2") (pintype "input"))
      (node (ref "U1") (pin "3") (pinfunction "LSA_3") (pintype "passive"))
      (node (ref "U1") (pin "4") (pinfunction "LSB_4") (pintype "passive"))
      (node (ref "U1") (pin "5") (pinfunction "LSC_5") (pintype "passive"))
      (node (ref "U2") (pin "96") (pinfunction "PB9_96") (pintype "bidirectional"))
    )
    (net (code "38") (name "/R_I") (class "Default")
      (node (ref "C20") (pin "1") (pinfunction "1_1") (pintype "passive"))
      (node (ref "R8") (pin "2") (pinfunction "2_2") (pintype "passive"))
      (node (ref "U2") (pin "17") (pinfunction "PC2_17") (pintype "bidirectional"))
    )
    (net (code "39") (name "/R_SCL") (class "Default")
      (node (ref "L_ENCODER1") (pin "3") (pinfunction "3_3") (pintype "passive"))
      (node (ref "R41") (pin "2") (pinfunction "2_2") (pintype "passive"))
      (node (ref "U2") (pin "98") (pinfunction "PE1_98") (pintype "bidirectional"))
    )
    (net (code "40") (name "/R_SDA") (class "Default")
      (node (ref "L_ENCODER1") (pin "2") (pinfunction "2_2") (pintype "passive"))
      (node (ref "R40") (pin "2") (pinfunction "2_2") (pintype "passive"))
      (node (ref "U2") (pin "97") (pinfunction "PE0_97") (pintype "bidirectional"))
    )
    (net (code "41") (name "/R_YA") (class "Default")
      (node (ref "U$2") (pin "P$3") (pinfunction "C_P$3") (pintype "input"))
      (node (ref "U1") (pin "26") (pinfunction "SA_26") (pintype "output"))
      (node (ref "U1") (pin "9") (pinfunction "SA_2_9") (pintype "output"))
    )
    (net (code "42") (name "/R_YB") (class "Default")
      (node (ref "U$2") (pin "P$2") (pinfunction "B_P$2") (pintype "input"))
      (node (ref "U1") (pin "11") (pinfunction "SB_2_11") (pintype "output"))
      (node (ref "U1") (pin "24") (pinfunction "SB_24") (pintype "output"))
    )
    (net (code "43") (name "/R_YC") (class "Default")
      (node (ref "U$2") (pin "P$1") (pinfunction "A_P$1") (pintype "input"))
      (node (ref "U1") (pin "13") (pinfunction "SC_2_13") (pintype "output"))
      (node (ref "U1") (pin "22") (pinfunction "SC_22") (pintype "output"))
    )
    (net (code "44") (name "/SCL") (class "Default")
      (node (ref "LSM6DS1") (pin "P$2") (pinfunction "SCL/SPC_P$2") (pintype "bidirectional"))
      (node (ref "R14") (pin "1") (pinfunction "1_1") (pintype "passive"))
      (node (ref "U2") (pin "83") (pinfunction "PD2_83") (pintype "bidirectional"))
    )
    (net (code "45") (name "/SDA") (class "Default")
      (node (ref "LSM6DS1") (pin "P$3") (pinfunction "SDA/SDI_P$3") (pintype "bidirectional"))
      (node (ref "R13") (pin "1") (pinfunction "1_1") (pintype "passive"))
      (node (ref "U2") (pin "82") (pinfunction "PD1_82") (pintype "bidirectional"))
    )
    (net (code "46") (name "/SWCLK") (class "Default")
      (node (ref "J1") (pin "4") (pinfunction "4_4") (pintype "passive"))
      (node (ref "U2") (pin "76") (pinfunction "PA14_76") (pintype "bidirectional"))
    )
    (net (code "47") (name "/SWDIO") (class "Default")
      (node (ref "J1") (pin "6") (pinfunction "6_6") (pintype "passive"))
      (node (ref "U2") (pin "72") (pinfunction "PA13_72") (pintype "bidirectional"))
    )
    (net (code "48") (name "/UART_RX") (class "Default")
      (node (ref "J1") (pin "3") (pinfunction "3_3") (pintype "passive"))
      (node (ref "U2") (pin "69") (pinfunction "PA10_69") (pintype "bidirectional"))
    )
    (net (code "49") (name "/UART_TX") (class "Default")
      (node (ref "J1") (pin "5") (pinfunction "5_5") (pintype "passive"))
      (node (ref "U2") (pin "68") (pinfunction "PA9_68") (pintype "bidirectional"))
    )
    (net (code "50") (name "/VBAT") (class "Default")
      (node (ref "U2") (pin "6") (pinfunction "VBAT_6") (pintype "power_in"))
    )
    (net (code "51") (name "GND") (class "Default")
      (node (ref "C1") (pin "2") (pinfunction "2_2") (pintype "passive"))
      (node (ref "C13") (pin "2") (pinfunction "2_2") (pintype "passive"))
      (node (ref "C14") (pin "1") (pinfunction "1_1") (pintype "passive"))
      (node (ref "C15") (pin "2") (pinfunction "2_2") (pintype "passive"))
      (node (ref "C16") (pin "2") (pinfunction "2_2") (pintype "passive"))
      (node (ref "C17") (pin "1") (pinfunction "1_1") (pintype "passive"))
      (node (ref "C18") (pin "1") (pinfunction "1_1") (pintype "passive"))
      (node (ref "C19") (pin "2") (pinfunction "2_2") (pintype "passive"))
      (node (ref "C20") (pin "2") (pinfunction "2_2") (pintype "passive"))
      (node (ref "C21") (pin "2") (pinfunction "2_2") (pintype "passive"))
      (node (ref "C22") (pin "2") (pinfunction "2_2") (pintype "passive"))
      (node (ref "C23") (pin "1") (pinfunction "1_1") (pintype "passive"))
      (node (ref "C24") (pin "2") (pinfunction "2_2") (pintype "passive"))
      (node (ref "C25") (pin "1") (pinfunction "1_1") (pintype "passive"))
      (node (ref "C26") (pin "1") (pinfunction "1_1") (pintype "passive"))
      (node (ref "C27") (pin "2") (pinfunction "2_2") (pintype "passive"))
      (node (ref "C28") (pin "2") (pinfunction "2_2") (pintype "passive"))
      (node (ref "C29") (pin "2") (pinfunction "2_2") (pintype "passive"))
      (node (ref "C32") (pin "1") (pinfunction "1_1") (pintype "passive"))
      (node (ref "C33") (pin "1") (pinfunction "1_1") (pintype "passive"))
      (node (ref "C34") (pin "-") (pinfunction "-_-") (pintype "passive"))
      (node (ref "C35") (pin "2") (pinfunction "2_2") (pintype "passive"))
      (node (ref "C36") (pin "2") (pinfunction "2_2") (pintype "passive"))
      (node (ref "C37") (pin "2") (pinfunction "2_2") (pintype "passive"))
      (node (ref "C38") (pin "2") (pinfunction "2_2") (pintype "passive"))
      (node (ref "C4") (pin "-") (pinfunction "-_-") (pintype "passive"))
      (node (ref "C40") (pin "1") (pinfunction "1_1") (pintype "passive"))
      (node (ref "C41") (pin "1") (pinfunction "1_1") (pintype "passive"))
      (node (ref "C42") (pin "1") (pinfunction "1_1") (pintype "passive"))
      (node (ref "C43") (pin "1") (pinfunction "1_1") (pintype "passive"))
      (node (ref "C44") (pin "1") (pinfunction "1_1") (pintype "passive"))
      (node (ref "C5") (pin "2") (pinfunction "2_2") (pintype "passive"))
      (node (ref "C6") (pin "2") (pinfunction "2_2") (pintype "passive"))
      (node (ref "C7") (pin "2") (pinfunction "2_2") (pintype "passive"))
      (node (ref "C8") (pin "2") (pinfunction "2_2") (pintype "passive"))
      (node (ref "IR_FRONT_S1") (pin "A") (pinfunction "A_A") (pintype "passive"))
      (node (ref "IR_FRONT_S2") (pin "A") (pinfunction "A_A") (pintype "passive"))
      (node (ref "IR_LEFT_S") (pin "A") (pinfunction "A_A") (pintype "passive"))
      (node (ref "IR_RIGHT_S") (pin "A") (pinfunction "A_A") (pintype "passive"))
      (node (ref "J1") (pin "7") (pinfunction "7_7") (pintype "passive"))
      (node (ref "J1") (pin "8") (pinfunction "8_8") (pintype "passive"))
      (node (ref "JP1") (pin "1") (pinfunction "1_1") (pintype "passive"))
      (node (ref "LED11") (pin "C") (pinfunction "C_C") (pintype "passive"))
      (node (ref "LED12") (pin "C") (pinfunction "C_C") (pintype "passive"))
      (node (ref "LSM6DS1") (pin "P$10") (pinfunction "RES2_P$10") (pintype "bidirectional"))
      (node (ref "LSM6DS1") (pin "P$11") (pinfunction "RES3_P$11") (pintype "bidirectional"))
      (node (ref "LSM6DS1") (pin "P$12") (pinfunction "GND_P$12") (pintype "power_in"))
      (node (ref "LSM6DS1") (pin "P$13") (pinfunction "GND_P$13") (pintype "power_in"))
      (node (ref "LSM6DS1") (pin "P$15") (pinfunction "RES4_P$15") (pintype "bidirectional"))
      (node (ref "LSM6DS1") (pin "P$4") (pinfunction "SDO_P$4") (pintype "bidirectional"))
      (node (ref "LSM6DS1") (pin "P$8") (pinfunction "DEN_P$8") (pintype "bidirectional"))
      (node (ref "LSM6DS1") (pin "P$9") (pinfunction "RES1_P$9") (pintype "bidirectional"))
      (node (ref "L_ENCODER") (pin "1") (pinfunction "1_1") (pintype "passive"))
      (node (ref "L_ENCODER1") (pin "1") (pinfunction "1_1") (pintype "passive"))
      (node (ref "Q10") (pin "E") (pinfunction "E_E") (pintype "passive"))
      (node (ref "Q11") (pin "E") (pinfunction "E_E") (pintype "passive"))
      (node (ref "Q2") (pin "2") (pinfunction "S_2") (pintype "passive"))
      (node (ref "Q3") (pin "2") (pinfunction "S_2") (pintype "passive"))
      (node (ref "Q4") (pin "E") (pinfunction "E_E") (pintype "passive"))
      (node (ref "Q5") (pin "E") (pinfunction "E_E") (pintype "passive"))
      (node (ref "Q6") (pin "E") (pinfunction "E_E") (pintype "passive"))
      (node (ref "Q7") (pin "E") (pinfunction "E_E") (pintype "passive"))
      (node (ref "Q8") (pin "E") (pinfunction "E_E") (pintype "passive"))
      (node (ref "Q9") (pin "E") (pinfunction "E_E") (pintype "passive"))
      (node (ref "R1") (pin "1") (pinfunction "1_1") (pintype "passive"))
      (node (ref "R3") (pin "1") (pinfunction "1_1") (pintype "passive"))
      (node (ref "R30") (pin "1") (pinfunction "1_1") (pintype "passive"))
      (node (ref "R36") (pin "1") (pinfunction "1_1") (pintype "passive"))
      (node (ref "RESET") (pin "1") (pinfunction "1_1") (pintype "passive"))
      (node (ref "RESET") (pin "2") (pinfunction "2_2") (pintype "passive"))
      (node (ref "U1") (pin "18") (pinfunction "GND_18") (pintype "passive"))
      (node (ref "U2") (pin "10") (pinfunction "VSS_2_10") (pintype "passive"))
      (node (ref "U2") (pin "19") (pinfunction "VSSA_19") (pintype "passive"))
      (node (ref "U2") (pin "26") (pinfunction "VSS_26") (pintype "passive"))
      (node (ref "U2") (pin "49") (pinfunction "VSS_4_49") (pintype "power_in"))
      (node (ref "U2") (pin "74") (pinfunction "VSS_2_74") (pintype "passive"))
      (node (ref "U2") (pin "99") (pinfunction "VSS_99") (pintype "passive"))
      (node (ref "U3") (pin "18") (pinfunction "GND_18") (pintype "passive"))
      (node (ref "U4") (pin "4") (pinfunction "GND_4") (pintype "bidirectional"))
      (node (ref "USER") (pin "1") (pinfunction "1_1") (pintype "passive"))
      (node (ref "USER") (pin "2") (pinfunction "2_2") (pintype "passive"))
    )
    (net (code "52") (name "Net-(IR_LEFT-PadA)") (class "Default")
      (node (ref "IR_LEFT") (pin "A") (pinfunction "A_A") (pintype "passive"))
      (node (ref "R33") (pin "1") (pinfunction "1_1") (pintype "passive"))
    )
    (net (code "53") (name "Net-(IR_RIGHT-PadA)") (class "Default")
      (node (ref "IR_RIGHT") (pin "A") (pinfunction "A_A") (pintype "passive"))
      (node (ref "R31") (pin "1") (pinfunction "1_1") (pintype "passive"))
    )
    (net (code "54") (name "Net-(IR_RIGHT1-PadA)") (class "Default")
      (node (ref "IR_RIGHT1") (pin "A") (pinfunction "A_A") (pintype "passive"))
      (node (ref "R29") (pin "1") (pinfunction "1_1") (pintype "passive"))
    )
    (net (code "55") (name "Net-(L1-1)") (class "Default")
      (node (ref "C39") (pin "1") (pinfunction "1_1") (pintype "passive"))
      (node (ref "L1") (pin "P$1") (pinfunction "1_P$1") (pintype "passive"))
      (node (ref "U4") (pin "5") (pinfunction "SW_5") (pintype "bidirectional"))
    )
    (net (code "56") (name "Net-(LED1-PadA)") (class "Default")
      (node (ref "LED1") (pin "A") (pinfunction "A_A") (pintype "passive"))
      (node (ref "R5") (pin "1") (pinfunction "1_1") (pintype "passive"))
    )
    (net (code "57") (name "Net-(LED2-PadA)") (class "Default")
      (node (ref "LED2") (pin "A") (pinfunction "A_A") (pintype "passive"))
      (node (ref "R10") (pin "1") (pinfunction "1_1") (pintype "passive"))
    )
    (net (code "58") (name "Net-(LED3-PadA)") (class "Default")
      (node (ref "LED3") (pin "A") (pinfunction "A_A") (pintype "passive"))
      (node (ref "R12") (pin "1") (pinfunction "1_1") (pintype "passive"))
    )
    (net (code "59") (name "Net-(LED4-PadA)") (class "Default")
      (node (ref "LED4") (pin "A") (pinfunction "A_A") (pintype "passive"))
      (node (ref "R17") (pin "1") (pinfunction "1_1") (pintype "passive"))
    )
    (net (code "60") (name "Net-(LED5-PadA)") (class "Default")
      (node (ref "LED5") (pin "A") (pinfunction "A_A") (pintype "passive"))
      (node (ref "R19") (pin "1") (pinfunction "1_1") (pintype "passive"))
    )
    (net (code "61") (name "Net-(LED6-PadA)") (class "Default")
      (node (ref "LED6") (pin "A") (pinfunction "A_A") (pintype "passive"))
      (node (ref "R21") (pin "1") (pinfunction "1_1") (pintype "passive"))
    )
    (net (code "62") (name "Net-(LED7-PadA)") (class "Default")
      (node (ref "LED7") (pin "A") (pinfunction "A_A") (pintype "passive"))
      (node (ref "R23") (pin "1") (pinfunction "1_1") (pintype "passive"))
    )
    (net (code "63") (name "Net-(LED8-PadA)") (class "Default")
      (node (ref "LED8") (pin "A") (pinfunction "A_A") (pintype "passive"))
      (node (ref "R25") (pin "1") (pinfunction "1_1") (pintype "passive"))
    )
    (net (code "64") (name "Net-(LED9-PadA)") (class "Default")
      (node (ref "LED9") (pin "A") (pinfunction "A_A") (pintype "passive"))
      (node (ref "R9") (pin "1") (pinfunction "1_1") (pintype "passive"))
    )
    (net (code "65") (name "Net-(LED11-PadA)") (class "Default")
      (node (ref "LED11") (pin "A") (pinfunction "A_A") (pintype "passive"))
      (node (ref "R28") (pin "1") (pinfunction "1_1") (pintype "passive"))
    )
    (net (code "66") (name "Net-(LED12-PadA)") (class "Default")
      (node (ref "LED12") (pin "A") (pinfunction "A_A") (pintype "passive"))
      (node (ref "R27") (pin "2") (pinfunction "2_2") (pintype "passive"))
    )
    (net (code "67") (name "Net-(LSM6DS1-CAP)") (class "Default")
      (node (ref "C14") (pin "2") (pinfunction "2_2") (pintype "passive"))
      (node (ref "LSM6DS1") (pin "P$14") (pinfunction "CAP_P$14") (pintype "bidirectional"))
    )
    (net (code "68") (name "Net-(U1-CP1)") (class "Default")
      (node (ref "C2") (pin "2") (pinfunction "2_2") (pintype "passive"))
      (node (ref "U1") (pin "20") (pinfunction "CP1_20") (pintype "passive"))
    )
    (net (code "69") (name "Net-(U1-CP2)") (class "Default")
      (node (ref "C2") (pin "1") (pinfunction "1_1") (pintype "passive"))
      (node (ref "U1") (pin "21") (pinfunction "CP2_21") (pintype "passive"))
    )
    (net (code "70") (name "Net-(U1-LSS)") (class "Default")
      (node (ref "R1") (pin "2") (pinfunction "2_2") (pintype "passive"))
      (node (ref "R8") (pin "1") (pinfunction "1_1") (pintype "passive"))
      (node (ref "U1") (pin "10") (pinfunction "LSS_2_10") (pintype "passive"))
      (node (ref "U1") (pin "12") (pinfunction "LSS_12") (pintype "passive"))
    )
    (net (code "71") (name "Net-(U1-VCP)") (class "Default")
      (node (ref "C3") (pin "1") (pinfunction "1_1") (pintype "passive"))
      (node (ref "U1") (pin "19") (pinfunction "VCP_19") (pintype "output"))
    )
    (net (code "72") (name "Net-(U1-VG)") (class "Default")
      (node (ref "C1") (pin "1") (pinfunction "1_1") (pintype "passive"))
      (node (ref "U1") (pin "14") (pinfunction "VG_14") (pintype "power_in"))
    )
    (net (code "73") (name "Net-(U2A-VCAP_1)") (class "Default")
      (node (ref "C23") (pin "2") (pinfunction "2_2") (pintype "passive"))
      (node (ref "U2") (pin "48") (pinfunction "VCAP_1_48") (pintype "power_in"))
    )
    (net (code "74") (name "Net-(U2B-VCAP_2)") (class "Default")
      (node (ref "C19") (pin "1") (pinfunction "1_1") (pintype "passive"))
      (node (ref "U2") (pin "73") (pinfunction "VCAP_2_73") (pintype "power_in"))
    )
    (net (code "75") (name "Net-(U3-CP1)") (class "Default")
      (node (ref "C30") (pin "2") (pinfunction "2_2") (pintype "passive"))
      (node (ref "U3") (pin "20") (pinfunction "CP1_20") (pintype "passive"))
    )
    (net (code "76") (name "Net-(U3-CP2)") (class "Default")
      (node (ref "C30") (pin "1") (pinfunction "1_1") (pintype "passive"))
      (node (ref "U3") (pin "21") (pinfunction "CP2_21") (pintype "passive"))
    )
    (net (code "77") (name "Net-(U3-LSS)") (class "Default")
      (node (ref "R36") (pin "2") (pinfunction "2_2") (pintype "passive"))
      (node (ref "R7") (pin "1") (pinfunction "1_1") (pintype "passive"))
      (node (ref "U3") (pin "10") (pinfunction "LSS_2_10") (pintype "passive"))
      (node (ref "U3") (pin "12") (pinfunction "LSS_12") (pintype "passive"))
    )
    (net (code "78") (name "Net-(U3-VCP)") (class "Default")
      (node (ref "C31") (pin "1") (pinfunction "1_1") (pintype "passive"))
      (node (ref "U3") (pin "19") (pinfunction "VCP_19") (pintype "output"))
    )
    (net (code "79") (name "Net-(U3-VG)") (class "Default")
      (node (ref "C13") (pin "1") (pinfunction "1_1") (pintype "passive"))
      (node (ref "U3") (pin "14") (pinfunction "VG_14") (pintype "power_in"))
    )
    (net (code "80") (name "Net-(U4-BST)") (class "Default")
      (node (ref "C39") (pin "2") (pinfunction "2_2") (pintype "passive"))
      (node (ref "U4") (pin "6") (pinfunction "BST_6") (pintype "bidirectional"))
    )
    (net (code "81") (name "VCC") (class "Default")
      (node (ref "C17") (pin "2") (pinfunction "2_2") (pintype "passive"))
      (node (ref "C18") (pin "2") (pinfunction "2_2") (pintype "passive"))
      (node (ref "C3") (pin "2") (pinfunction "2_2") (pintype "passive"))
      (node (ref "C31") (pin "2") (pinfunction "2_2") (pintype "passive"))
      (node (ref "C32") (pin "2") (pinfunction "2_2") (pintype "passive"))
      (node (ref "C33") (pin "2") (pinfunction "2_2") (pintype "passive"))
      (node (ref "C34") (pin "+") (pinfunction "+_+") (pintype "passive"))
      (node (ref "C4") (pin "+") (pinfunction "+_+") (pintype "passive"))
      (node (ref "C40") (pin "2") (pinfunction "2_2") (pintype "passive"))
      (node (ref "C41") (pin "2") (pinfunction "2_2") (pintype "passive"))
      (node (ref "JP1") (pin "2") (pinfunction "2_2") (pintype "passive"))
      (node (ref "U1") (pin "23") (pinfunction "VIN_2_23") (pintype "power_in"))
      (node (ref "U1") (pin "25") (pinfunction "VIN_25") (pintype "power_in"))
      (node (ref "U3") (pin "23") (pinfunction "VIN_2_23") (pintype "power_in"))
      (node (ref "U3") (pin "25") (pinfunction "VIN_25") (pintype "power_in"))
      (node (ref "U4") (pin "2") (pinfunction "EN_2") (pintype "bidirectional"))
      (node (ref "U4") (pin "3") (pinfunction "VIN_3") (pintype "bidirectional"))
    )
    (net (code "82") (name "unconnected-(LSM6DS1-DRDY{slash}INT2-PadP$6)") (class "Default")
      (node (ref "LSM6DS1") (pin "P$6") (pinfunction "DRDY/INT2_P$6") (pintype "bidirectional"))
    )
    (net (code "83") (name "unconnected-(LSM6DS1-INT1-PadP$7)") (class "Default")
      (node (ref "LSM6DS1") (pin "P$7") (pinfunction "INT1_P$7") (pintype "bidirectional"))
    )
    (net (code "84") (name "unconnected-(U1-NFAULT-Pad1)") (class "Default")
      (node (ref "U1") (pin "1") (pinfunction "NFAULT_1") (pintype "output"))
    )
    (net (code "85") (name "unconnected-(U1-SOA-Pad15)") (class "Default")
      (node (ref "U1") (pin "15") (pinfunction "SOA_15") (pintype "output"))
    )
    (net (code "86") (name "unconnected-(U1-SOB-Pad16)") (class "Default")
      (node (ref "U1") (pin "16") (pinfunction "SOB_16") (pintype "output"))
    )
    (net (code "87") (name "unconnected-(U1-SOC-Pad17)") (class "Default")
      (node (ref "U1") (pin "17") (pinfunction "SOC_17") (pintype "output"))
    )
    (net (code "88") (name "unconnected-(U2A-PB2-Pad36)") (class "Default")
      (node (ref "U2") (pin "36") (pinfunction "PB2_36") (pintype "bidirectional"))
    )
    (net (code "89") (name "unconnected-(U2A-PB10-Pad46)") (class "Default")
      (node (ref "U2") (pin "46") (pinfunction "PB10_46") (pintype "bidirectional"))
    )
    (net (code "90") (name "unconnected-(U2A-PB11-Pad47)") (class "Default")
      (node (ref "U2") (pin "47") (pinfunction "PB11_47") (pintype "bidirectional"))
    )
    (net (code "91") (name "unconnected-(U2A-PC0-Pad15)") (class "Default")
      (node (ref "U2") (pin "15") (pinfunction "PC0_15") (pintype "bidirectional"))
    )
    (net (code "92") (name "unconnected-(U2A-PC1-Pad16)") (class "Default")
      (node (ref "U2") (pin "16") (pinfunction "PC1_16") (pintype "bidirectional"))
    )
    (net (code "93") (name "unconnected-(U2A-PC13-Pad7)") (class "Default")
      (node (ref "U2") (pin "7") (pinfunction "PC13_7") (pintype "bidirectional"))
    )
    (net (code "94") (name "unconnected-(U2A-PE4-Pad3)") (class "Default")
      (node (ref "U2") (pin "3") (pinfunction "PE4_3") (pintype "bidirectional"))
    )
    (net (code "95") (name "unconnected-(U2A-PE5-Pad4)") (class "Default")
      (node (ref "U2") (pin "4") (pinfunction "PE5_4") (pintype "bidirectional"))
    )
    (net (code "96") (name "unconnected-(U2A-PE6-Pad5)") (class "Default")
      (node (ref "U2") (pin "5") (pinfunction "PE6_5") (pintype "bidirectional"))
    )
    (net (code "97") (name "unconnected-(U2A-PE7-Pad37)") (class "Default")
      (node (ref "U2") (pin "37") (pinfunction "PE7_37") (pintype "bidirectional"))
    )
    (net (code "98") (name "unconnected-(U2A-PE8-Pad38)") (class "Default")
      (node (ref "U2") (pin "38") (pinfunction "PE8_38") (pintype "bidirectional"))
    )
    (net (code "99") (name "unconnected-(U2A-PE9-Pad39)") (class "Default")
      (node (ref "U2") (pin "39") (pinfunction "PE9_39") (pintype "bidirectional"))
    )
    (net (code "100") (name "unconnected-(U2A-PE10-Pad40)") (class "Default")
      (node (ref "U2") (pin "40") (pinfunction "PE10_40") (pintype "bidirectional"))
    )
    (net (code "101") (name "unconnected-(U2A-PE11-Pad41)") (class "Default")
      (node (ref "U2") (pin "41") (pinfunction "PE11_41") (pintype "bidirectional"))
    )
    (net (code "102") (name "unconnected-(U2A-PE12-Pad42)") (class "Default")
      (node (ref "U2") (pin "42") (pinfunction "PE12_42") (pintype "bidirectional"))
    )
    (net (code "103") (name "unconnected-(U2A-PE13-Pad43)") (class "Default")
      (node (ref "U2") (pin "43") (pinfunction "PE13_43") (pintype "bidirectional"))
    )
    (net (code "104") (name "unconnected-(U2A-PE14-Pad44)") (class "Default")
      (node (ref "U2") (pin "44") (pinfunction "PE14_44") (pintype "bidirectional"))
    )
    (net (code "105") (name "unconnected-(U2A-PE15-Pad45)") (class "Default")
      (node (ref "U2") (pin "45") (pinfunction "PE15_45") (pintype "bidirectional"))
    )
    (net (code "106") (name "unconnected-(U2B-PA12-Pad71)") (class "Default")
      (node (ref "U2") (pin "71") (pinfunction "PA12_71") (pintype "bidirectional"))
    )
    (net (code "107") (name "unconnected-(U2B-PA15-Pad77)") (class "Default")
      (node (ref "U2") (pin "77") (pinfunction "PA15_77") (pintype "bidirectional"))
    )
    (net (code "108") (name "unconnected-(U2B-PA_11-Pad70)") (class "Default")
      (node (ref "U2") (pin "70") (pinfunction "PA_11_70") (pintype "bidirectional"))
    )
    (net (code "109") (name "unconnected-(U2B-PB3-Pad89)") (class "Default")
      (node (ref "U2") (pin "89") (pinfunction "PB3_89") (pintype "bidirectional"))
    )
    (net (code "110") (name "unconnected-(U2B-PB4-Pad90)") (class "Default")
      (node (ref "U2") (pin "90") (pinfunction "PB4_90") (pintype "bidirectional"))
    )
    (net (code "111") (name "unconnected-(U2B-PB5-Pad91)") (class "Default")
      (node (ref "U2") (pin "91") (pinfunction "PB5_91") (pintype "bidirectional"))
    )
    (net (code "112") (name "unconnected-(U2B-PB12-Pad51)") (class "Default")
      (node (ref "U2") (pin "51") (pinfunction "PB12_51") (pintype "bidirectional"))
    )
    (net (code "113") (name "unconnected-(U2B-PB13-Pad52)") (class "Default")
      (node (ref "U2") (pin "52") (pinfunction "PB13_52") (pintype "bidirectional"))
    )
    (net (code "114") (name "unconnected-(U2B-PB14-Pad53)") (class "Default")
      (node (ref "U2") (pin "53") (pinfunction "PB14_53") (pintype "bidirectional"))
    )
    (net (code "115") (name "unconnected-(U2B-PB15-Pad54)") (class "Default")
      (node (ref "U2") (pin "54") (pinfunction "PB15_54") (pintype "bidirectional"))
    )
    (net (code "116") (name "unconnected-(U2B-PC6-Pad63)") (class "Default")
      (node (ref "U2") (pin "63") (pinfunction "PC6_63") (pintype "bidirectional"))
    )
    (net (code "117") (name "unconnected-(U2B-PC10-Pad78)") (class "Default")
      (node (ref "U2") (pin "78") (pinfunction "PC10_78") (pintype "bidirectional"))
    )
    (net (code "118") (name "unconnected-(U2B-PC11-Pad79)") (class "Default")
      (node (ref "U2") (pin "79") (pinfunction "PC11_79") (pintype "bidirectional"))
    )
    (net (code "119") (name "unconnected-(U2B-PC12-Pad80)") (class "Default")
      (node (ref "U2") (pin "80") (pinfunction "PC12_80") (pintype "bidirectional"))
    )
    (net (code "120") (name "unconnected-(U2B-PD0-Pad81)") (class "Default")
      (node (ref "U2") (pin "81") (pinfunction "PD0_81") (pintype "bidirectional"))
    )
    (net (code "121") (name "unconnected-(U2B-PD3-Pad84)") (class "Default")
      (node (ref "U2") (pin "84") (pinfunction "PD3_84") (pintype "bidirectional"))
    )
    (net (code "122") (name "unconnected-(U2B-PD4-Pad85)") (class "Default")
      (node (ref "U2") (pin "85") (pinfunction "PD4_85") (pintype "bidirectional"))
    )
    (net (code "123") (name "unconnected-(U2B-PD5-Pad86)") (class "Default")
      (node (ref "U2") (pin "86") (pinfunction "PD5_86") (pintype "bidirectional"))
    )
    (net (code "124") (name "unconnected-(U2B-PD6-Pad87)") (class "Default")
      (node (ref "U2") (pin "87") (pinfunction "PD6_87") (pintype "bidirectional"))
    )
    (net (code "125") (name "unconnected-(U2B-PD7-Pad88)") (class "Default")
      (node (ref "U2") (pin "88") (pinfunction "PD7_88") (pintype "bidirectional"))
    )
    (net (code "126") (name "unconnected-(U2B-PD8-Pad55)") (class "Default")
      (node (ref "U2") (pin "55") (pinfunction "PD8_55") (pintype "bidirectional"))
    )
    (net (code "127") (name "unconnected-(U2B-PD9-Pad56)") (class "Default")
      (node (ref "U2") (pin "56") (pinfunction "PD9_56") (pintype "bidirectional"))
    )
    (net (code "128") (name "unconnected-(U2B-PD10-Pad57)") (class "Default")
      (node (ref "U2") (pin "57") (pinfunction "PD10_57") (pintype "bidirectional"))
    )
    (net (code "129") (name "unconnected-(U2B-PD11-Pad58)") (class "Default")
      (node (ref "U2") (pin "58") (pinfunction "PD11_58") (pintype "bidirectional"))
    )
    (net (code "130") (name "unconnected-(U2B-PD12-Pad59)") (class "Default")
      (node (ref "U2") (pin "59") (pinfunction "PD12_59") (pintype "bidirectional"))
    )
    (net (code "131") (name "unconnected-(U2B-PD13-Pad60)") (class "Default")
      (node (ref "U2") (pin "60") (pinfunction "PD13_60") (pintype "bidirectional"))
    )
    (net (code "132") (name "unconnected-(U3-NFAULT-Pad1)") (class "Default")
      (node (ref "U3") (pin "1") (pinfunction "NFAULT_1") (pintype "output"))
    )
    (net (code "133") (name "unconnected-(U3-SOA-Pad15)") (class "Default")
      (node (ref "U3") (pin "15") (pinfunction "SOA_15") (pintype "output"))
    )
    (net (code "134") (name "unconnected-(U3-SOB-Pad16)") (class "Default")
      (node (ref "U3") (pin "16") (pinfunction "SOB_16") (pintype "output"))
    )
    (net (code "135") (name "unconnected-(U3-SOC-Pad17)") (class "Default")
      (node (ref "U3") (pin "17") (pinfunction "SOC_17") (pintype "output"))
    )
    (net (code "136") (name "unconnected-(USER-Pad3)") (class "Default")
      (node (ref "USER") (pin "3") (pinfunction "3_3") (pintype "passive"))
    )
  )
)
